# multiple_valve_controller_v2_0.net
KiCad netlist of a schematic drawn in EAGLE
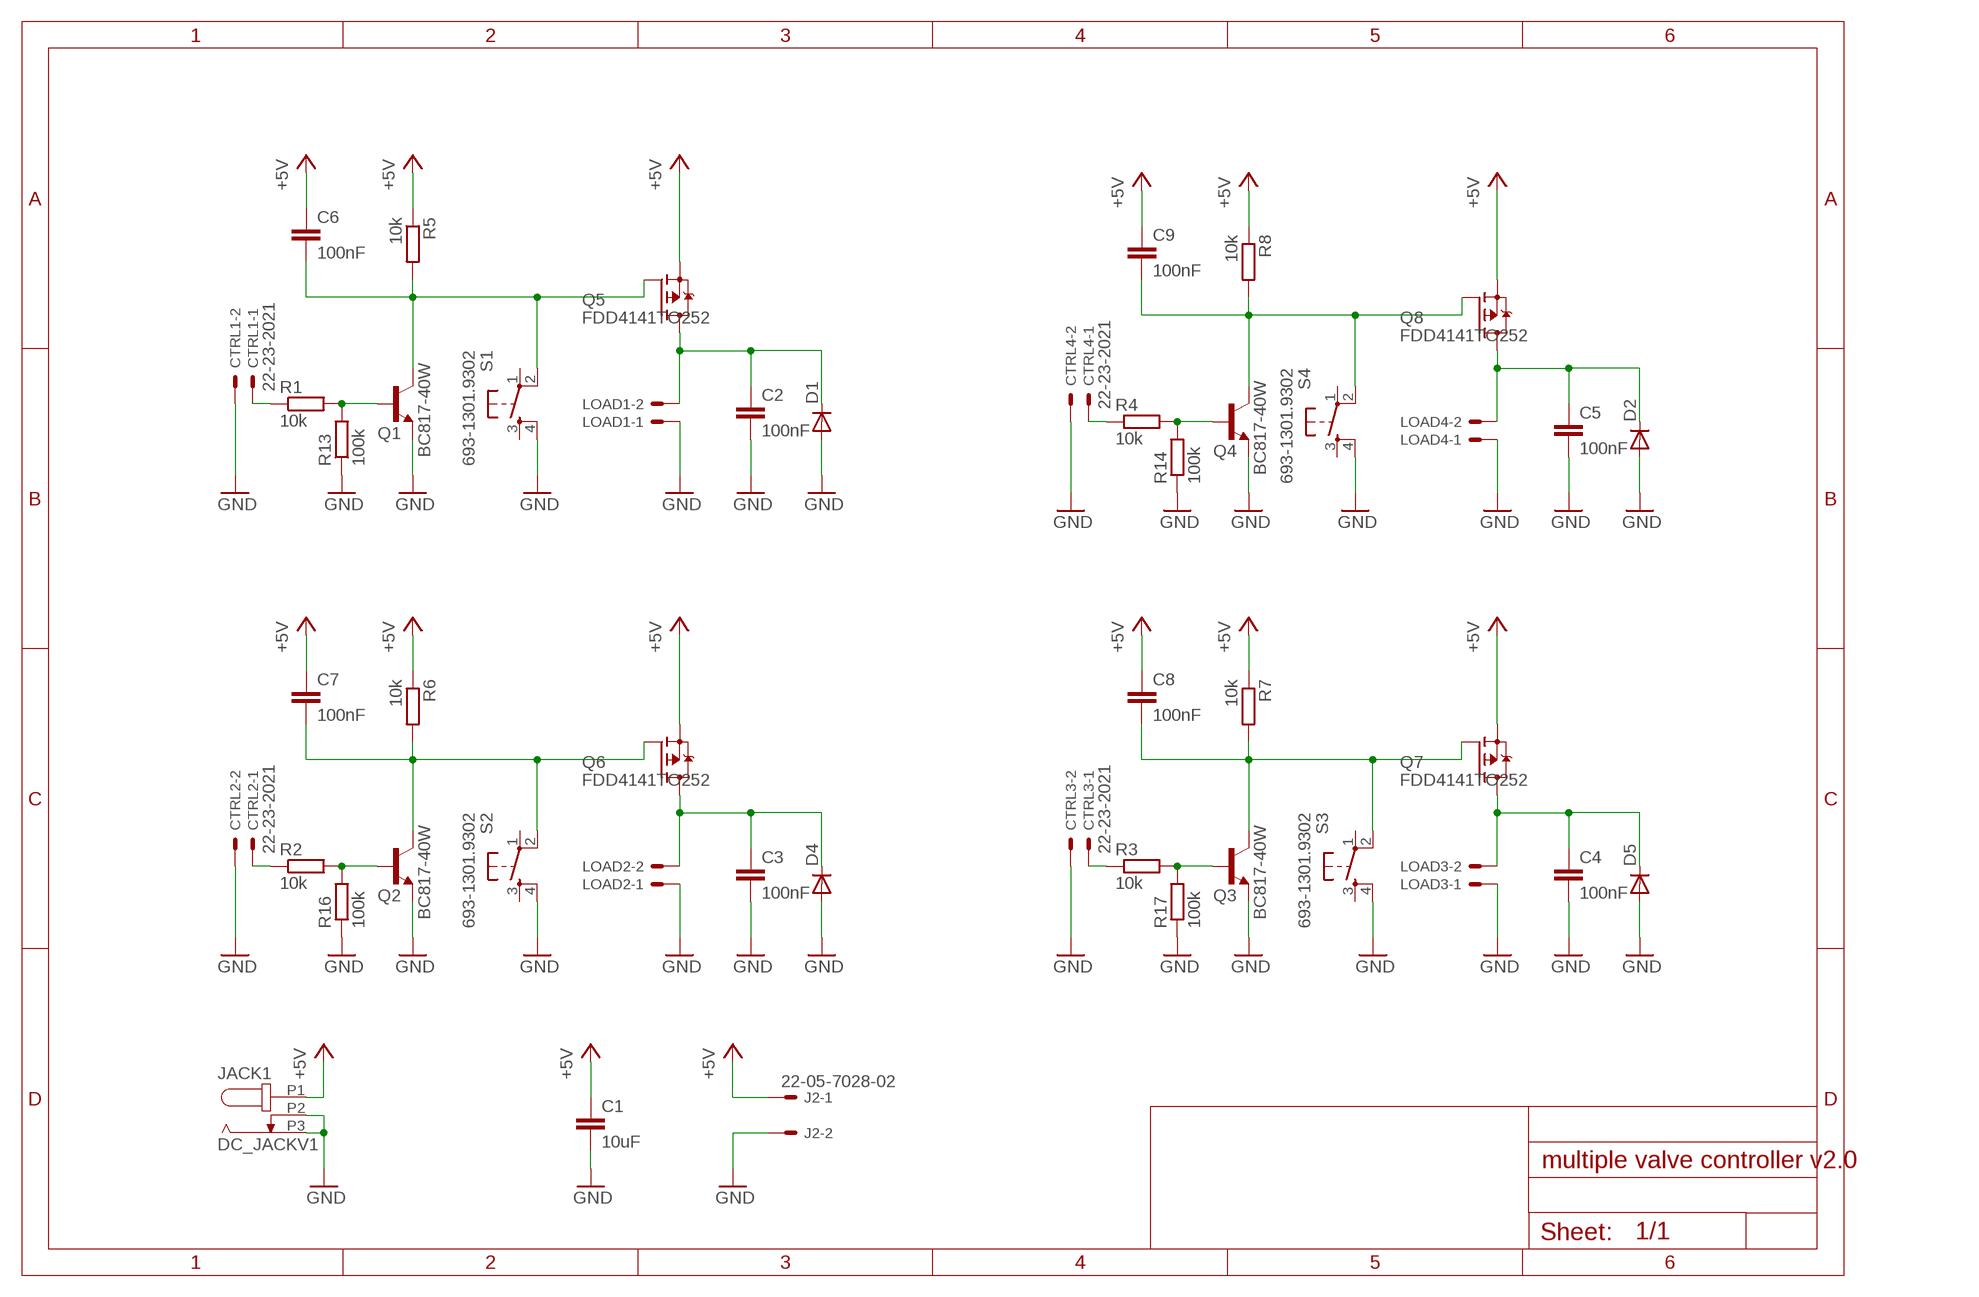
[diagram p0: schematic, sheet 1, part 1 of 2]
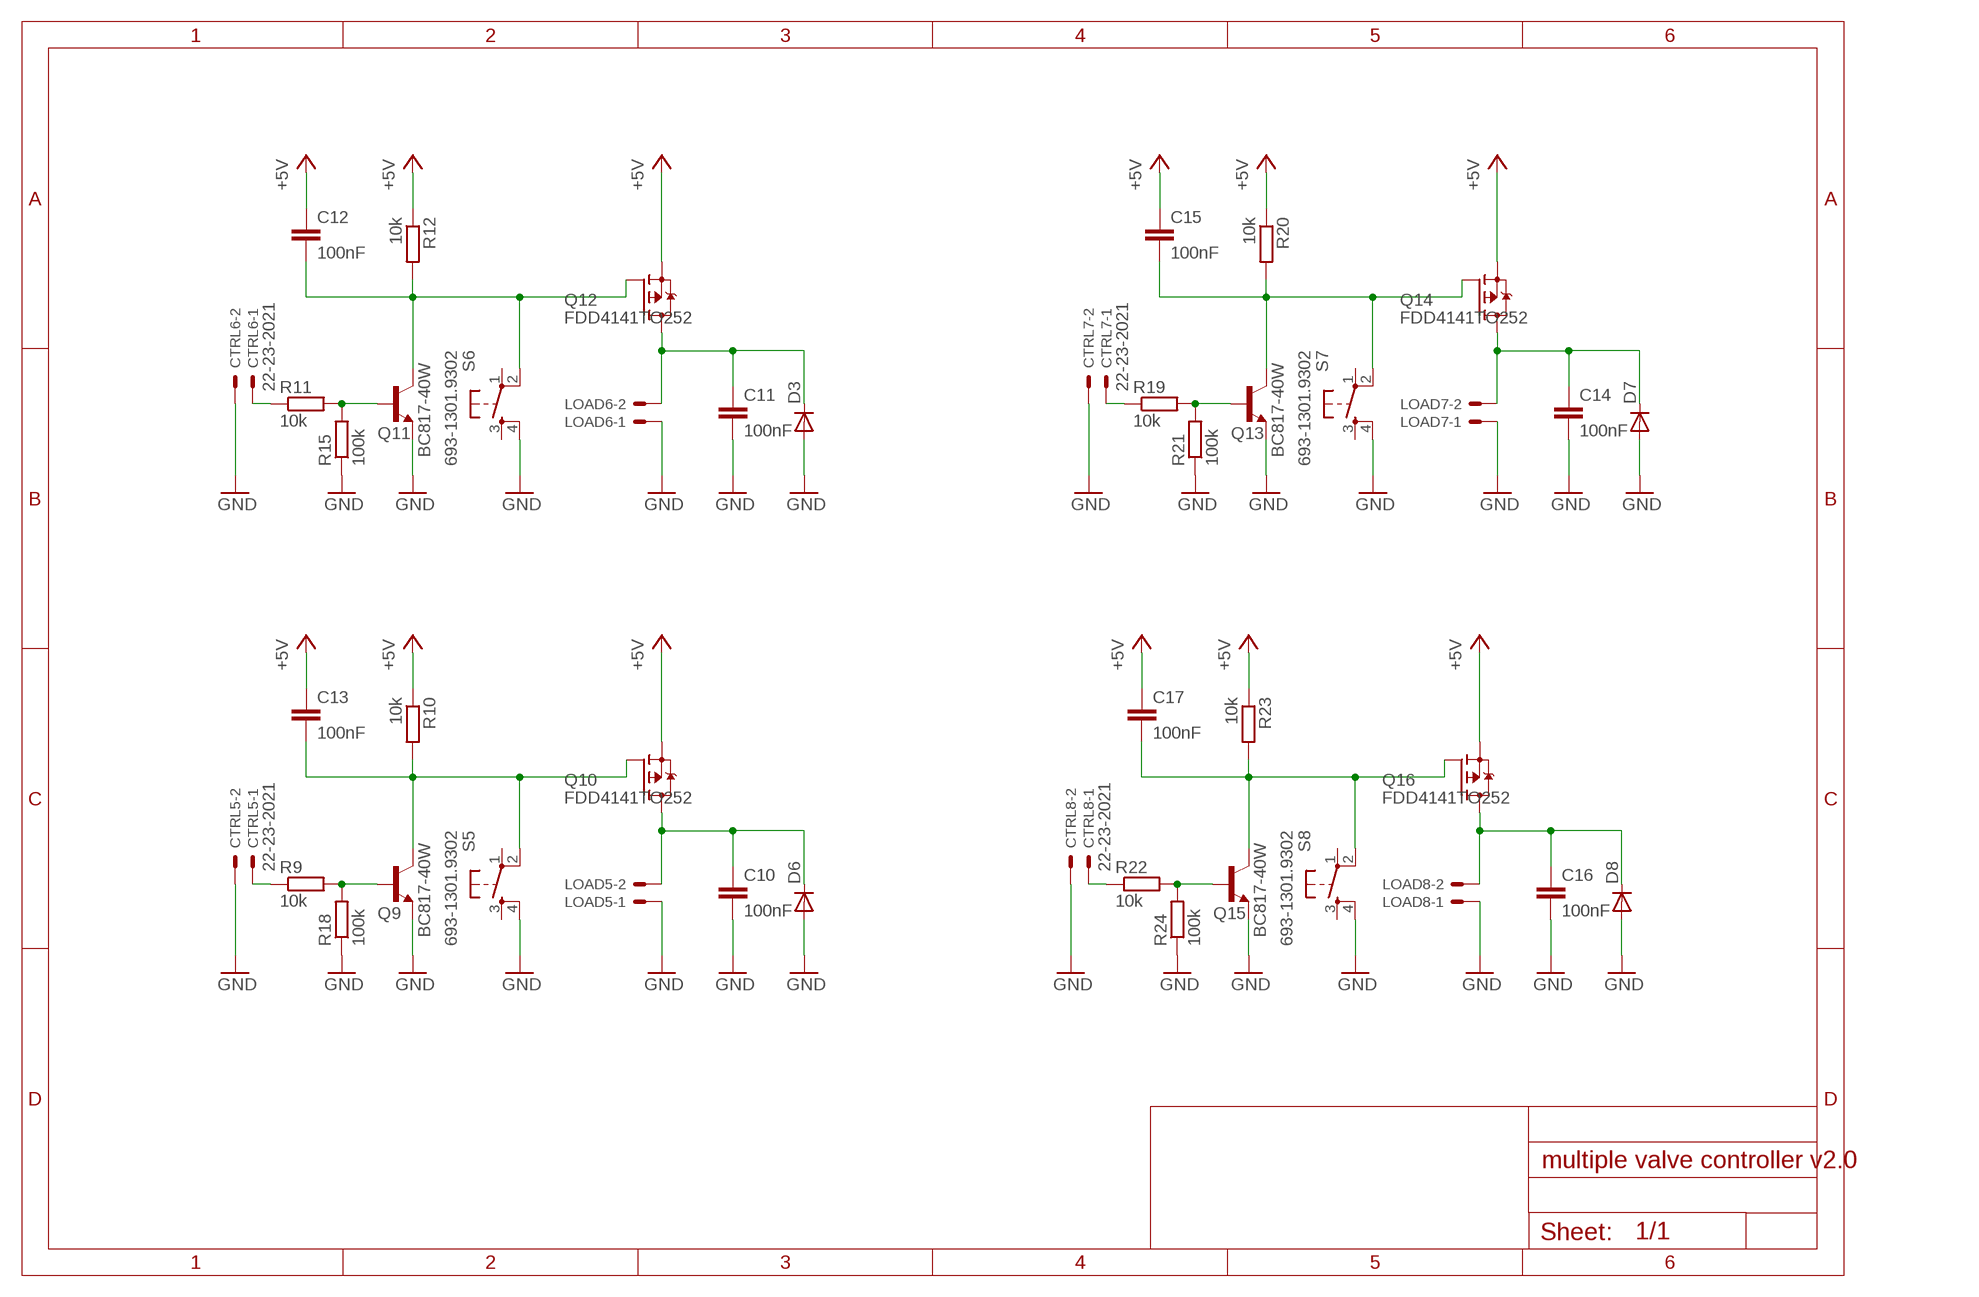
[diagram p1: schematic, sheet 1, part 2 of 2]

(export (version "E")
  (design (tool "Eeschema 10.0.6"))
  (components
    (comp (ref "C1")
      (value "10uF")
      (footprint "eagle-import:C1210")
      (libsource (lib "eagle-import") (part "C-EUC1210"))
    )
    (comp (ref "C2")
      (value "100nF")
      (footprint "eagle-import:C1210")
      (libsource (lib "eagle-import") (part "C-EUC1210"))
    )
    (comp (ref "C3")
      (value "100nF")
      (footprint "eagle-import:C1210")
      (libsource (lib "eagle-import") (part "C-EUC1210"))
    )
    (comp (ref "C4")
      (value "100nF")
      (footprint "eagle-import:C1210")
      (libsource (lib "eagle-import") (part "C-EUC1210"))
    )
    (comp (ref "C5")
      (value "100nF")
      (footprint "eagle-import:C1210")
      (libsource (lib "eagle-import") (part "C-EUC1210"))
    )
    (comp (ref "C6")
      (value "100nF")
      (footprint "eagle-import:C0603")
      (libsource (lib "eagle-import") (part "C-EUC0603"))
    )
    (comp (ref "C7")
      (value "100nF")
      (footprint "eagle-import:C0603")
      (libsource (lib "eagle-import") (part "C-EUC0603"))
    )
    (comp (ref "C8")
      (value "100nF")
      (footprint "eagle-import:C0603")
      (libsource (lib "eagle-import") (part "C-EUC0603"))
    )
    (comp (ref "C9")
      (value "100nF")
      (footprint "eagle-import:C0603")
      (libsource (lib "eagle-import") (part "C-EUC0603"))
    )
    (comp (ref "C10")
      (value "100nF")
      (footprint "eagle-import:C1210")
      (libsource (lib "eagle-import") (part "C-EUC1210"))
    )
    (comp (ref "C11")
      (value "100nF")
      (footprint "eagle-import:C1210")
      (libsource (lib "eagle-import") (part "C-EUC1210"))
    )
    (comp (ref "C12")
      (value "100nF")
      (footprint "eagle-import:C0603")
      (libsource (lib "eagle-import") (part "C-EUC0603"))
    )
    (comp (ref "C13")
      (value "100nF")
      (footprint "eagle-import:C0603")
      (libsource (lib "eagle-import") (part "C-EUC0603"))
    )
    (comp (ref "C14")
      (value "100nF")
      (footprint "eagle-import:C1210")
      (libsource (lib "eagle-import") (part "C-EUC1210"))
    )
    (comp (ref "C15")
      (value "100nF")
      (footprint "eagle-import:C0603")
      (libsource (lib "eagle-import") (part "C-EUC0603"))
    )
    (comp (ref "C16")
      (value "100nF")
      (footprint "eagle-import:C1210")
      (libsource (lib "eagle-import") (part "C-EUC1210"))
    )
    (comp (ref "C17")
      (value "100nF")
      (footprint "eagle-import:C0603")
      (libsource (lib "eagle-import") (part "C-EUC0603"))
    )
    (comp (ref "CTRL1")
      (value "22-23-2021")
      (footprint "eagle-import:22-23-2021")
      (fields (field (name "MF") "MOLEX"))
      (libsource (lib "eagle-import") (part "con-molex_165_22-23-2021"))
    )
    (comp (ref "CTRL2")
      (value "22-23-2021")
      (footprint "eagle-import:22-23-2021")
      (fields (field (name "MF") "MOLEX"))
      (libsource (lib "eagle-import") (part "con-molex_165_22-23-2021"))
    )
    (comp (ref "CTRL3")
      (value "22-23-2021")
      (footprint "eagle-import:22-23-2021")
      (fields (field (name "MF") "MOLEX"))
      (libsource (lib "eagle-import") (part "con-molex_165_22-23-2021"))
    )
    (comp (ref "CTRL4")
      (value "22-23-2021")
      (footprint "eagle-import:22-23-2021")
      (fields (field (name "MF") "MOLEX"))
      (libsource (lib "eagle-import") (part "con-molex_165_22-23-2021"))
    )
    (comp (ref "CTRL5")
      (value "22-23-2021")
      (footprint "eagle-import:22-23-2021")
      (fields (field (name "MF") "MOLEX"))
      (libsource (lib "eagle-import") (part "con-molex_165_22-23-2021"))
    )
    (comp (ref "CTRL6")
      (value "22-23-2021")
      (footprint "eagle-import:22-23-2021")
      (fields (field (name "MF") "MOLEX"))
      (libsource (lib "eagle-import") (part "con-molex_165_22-23-2021"))
    )
    (comp (ref "CTRL7")
      (value "22-23-2021")
      (footprint "eagle-import:22-23-2021")
      (fields (field (name "MF") "MOLEX"))
      (libsource (lib "eagle-import") (part "con-molex_165_22-23-2021"))
    )
    (comp (ref "CTRL8")
      (value "22-23-2021")
      (footprint "eagle-import:22-23-2021")
      (fields (field (name "MF") "MOLEX"))
      (libsource (lib "eagle-import") (part "con-molex_165_22-23-2021"))
    )
    (comp (ref "D1")
      (value "DIODE-SOD323-R")
      (footprint "eagle-import:SOD323-R")
      (libsource (lib "eagle-import") (part "DIODE-SOD323-R"))
    )
    (comp (ref "D2")
      (value "DIODE-SOD323-R")
      (footprint "eagle-import:SOD323-R")
      (libsource (lib "eagle-import") (part "DIODE-SOD323-R"))
    )
    (comp (ref "D3")
      (value "DIODE-SOD323-R")
      (footprint "eagle-import:SOD323-R")
      (libsource (lib "eagle-import") (part "DIODE-SOD323-R"))
    )
    (comp (ref "D4")
      (value "DIODE-SOD323-R")
      (footprint "eagle-import:SOD323-R")
      (libsource (lib "eagle-import") (part "DIODE-SOD323-R"))
    )
    (comp (ref "D5")
      (value "DIODE-SOD323-R")
      (footprint "eagle-import:SOD323-R")
      (libsource (lib "eagle-import") (part "DIODE-SOD323-R"))
    )
    (comp (ref "D6")
      (value "DIODE-SOD323-R")
      (footprint "eagle-import:SOD323-R")
      (libsource (lib "eagle-import") (part "DIODE-SOD323-R"))
    )
    (comp (ref "D7")
      (value "DIODE-SOD323-R")
      (footprint "eagle-import:SOD323-R")
      (libsource (lib "eagle-import") (part "DIODE-SOD323-R"))
    )
    (comp (ref "D8")
      (value "DIODE-SOD323-R")
      (footprint "eagle-import:SOD323-R")
      (libsource (lib "eagle-import") (part "DIODE-SOD323-R"))
    )
    (comp (ref "J2")
      (value "22-05-7028-02")
      (footprint "eagle-import:7395-02")
      (libsource (lib "eagle-import") (part "22-?-0205-7028"))
    )
    (comp (ref "JACK1")
      (value "DC_JACKV1")
      (footprint "eagle-import:DC_POWER_INPUT")
      (libsource (lib "eagle-import") (part "DC_JACKV1"))
    )
    (comp (ref "LOAD1")
      (value "22-23-2021")
      (footprint "eagle-import:22-23-2021")
      (fields (field (name "MF") "MOLEX"))
      (libsource (lib "eagle-import") (part "22-23-2021"))
    )
    (comp (ref "LOAD2")
      (value "22-23-2021")
      (footprint "eagle-import:22-23-2021")
      (fields (field (name "MF") "MOLEX"))
      (libsource (lib "eagle-import") (part "22-23-2021"))
    )
    (comp (ref "LOAD3")
      (value "22-23-2021")
      (footprint "eagle-import:22-23-2021")
      (fields (field (name "MF") "MOLEX"))
      (libsource (lib "eagle-import") (part "22-23-2021"))
    )
    (comp (ref "LOAD4")
      (value "22-23-2021")
      (footprint "eagle-import:22-23-2021")
      (fields (field (name "MF") "MOLEX"))
      (libsource (lib "eagle-import") (part "22-23-2021"))
    )
    (comp (ref "LOAD5")
      (value "22-23-2021")
      (footprint "eagle-import:22-23-2021")
      (fields (field (name "MF") "MOLEX"))
      (libsource (lib "eagle-import") (part "22-23-2021"))
    )
    (comp (ref "LOAD6")
      (value "22-23-2021")
      (footprint "eagle-import:22-23-2021")
      (fields (field (name "MF") "MOLEX"))
      (libsource (lib "eagle-import") (part "22-23-2021"))
    )
    (comp (ref "LOAD7")
      (value "22-23-2021")
      (footprint "eagle-import:22-23-2021")
      (fields (field (name "MF") "MOLEX"))
      (libsource (lib "eagle-import") (part "22-23-2021"))
    )
    (comp (ref "LOAD8")
      (value "22-23-2021")
      (footprint "eagle-import:22-23-2021")
      (fields (field (name "MF") "MOLEX"))
      (libsource (lib "eagle-import") (part "22-23-2021"))
    )
    (comp (ref "Q1")
      (value "BC817-40W")
      (footprint "eagle-import:SOT323-BEC")
      (libsource (lib "eagle-import") (part "BC817"))
    )
    (comp (ref "Q2")
      (value "BC817-40W")
      (footprint "eagle-import:SOT323-BEC")
      (libsource (lib "eagle-import") (part "BC817"))
    )
    (comp (ref "Q3")
      (value "BC817-40W")
      (footprint "eagle-import:SOT323-BEC")
      (libsource (lib "eagle-import") (part "BC817"))
    )
    (comp (ref "Q4")
      (value "BC817-40W")
      (footprint "eagle-import:SOT323-BEC")
      (libsource (lib "eagle-import") (part "BC817"))
    )
    (comp (ref "Q5")
      (value "FDD4141TO252")
      (footprint "eagle-import:TO252")
      (libsource (lib "eagle-import") (part "FDD4141TO252"))
    )
    (comp (ref "Q6")
      (value "FDD4141TO252")
      (footprint "eagle-import:TO252")
      (libsource (lib "eagle-import") (part "FDD4141TO252"))
    )
    (comp (ref "Q7")
      (value "FDD4141TO252")
      (footprint "eagle-import:TO252")
      (libsource (lib "eagle-import") (part "FDD4141TO252"))
    )
    (comp (ref "Q8")
      (value "FDD4141TO252")
      (footprint "eagle-import:TO252")
      (libsource (lib "eagle-import") (part "FDD4141TO252"))
    )
    (comp (ref "Q9")
      (value "BC817-40W")
      (footprint "eagle-import:SOT323-BEC")
      (libsource (lib "eagle-import") (part "BC817"))
    )
    (comp (ref "Q10")
      (value "FDD4141TO252")
      (footprint "eagle-import:TO252")
      (libsource (lib "eagle-import") (part "FDD4141TO252"))
    )
    (comp (ref "Q11")
      (value "BC817-40W")
      (footprint "eagle-import:SOT323-BEC")
      (libsource (lib "eagle-import") (part "BC817"))
    )
    (comp (ref "Q12")
      (value "FDD4141TO252")
      (footprint "eagle-import:TO252")
      (libsource (lib "eagle-import") (part "FDD4141TO252"))
    )
    (comp (ref "Q13")
      (value "BC817-40W")
      (footprint "eagle-import:SOT323-BEC")
      (libsource (lib "eagle-import") (part "BC817"))
    )
    (comp (ref "Q14")
      (value "FDD4141TO252")
      (footprint "eagle-import:TO252")
      (libsource (lib "eagle-import") (part "FDD4141TO252"))
    )
    (comp (ref "Q15")
      (value "BC817-40W")
      (footprint "eagle-import:SOT323-BEC")
      (libsource (lib "eagle-import") (part "BC817"))
    )
    (comp (ref "Q16")
      (value "FDD4141TO252")
      (footprint "eagle-import:TO252")
      (libsource (lib "eagle-import") (part "FDD4141TO252"))
    )
    (comp (ref "R1")
      (value "10k")
      (footprint "eagle-import:R0402")
      (libsource (lib "eagle-import") (part "R-EU_R0402"))
    )
    (comp (ref "R2")
      (value "10k")
      (footprint "eagle-import:R0402")
      (libsource (lib "eagle-import") (part "R-EU_R0402"))
    )
    (comp (ref "R3")
      (value "10k")
      (footprint "eagle-import:R0402")
      (libsource (lib "eagle-import") (part "R-EU_R0402"))
    )
    (comp (ref "R4")
      (value "10k")
      (footprint "eagle-import:R0402")
      (libsource (lib "eagle-import") (part "R-EU_R0402"))
    )
    (comp (ref "R5")
      (value "10k")
      (footprint "eagle-import:R0603")
      (libsource (lib "eagle-import") (part "R-EU_R0603"))
    )
    (comp (ref "R6")
      (value "10k")
      (footprint "eagle-import:R0603")
      (libsource (lib "eagle-import") (part "R-EU_R0603"))
    )
    (comp (ref "R7")
      (value "10k")
      (footprint "eagle-import:R0603")
      (libsource (lib "eagle-import") (part "R-EU_R0603"))
    )
    (comp (ref "R8")
      (value "10k")
      (footprint "eagle-import:R0603")
      (libsource (lib "eagle-import") (part "R-EU_R0603"))
    )
    (comp (ref "R9")
      (value "10k")
      (footprint "eagle-import:R0402")
      (libsource (lib "eagle-import") (part "R-EU_R0402"))
    )
    (comp (ref "R10")
      (value "10k")
      (footprint "eagle-import:R0603")
      (libsource (lib "eagle-import") (part "R-EU_R0603"))
    )
    (comp (ref "R11")
      (value "10k")
      (footprint "eagle-import:R0402")
      (libsource (lib "eagle-import") (part "R-EU_R0402"))
    )
    (comp (ref "R12")
      (value "10k")
      (footprint "eagle-import:R0603")
      (libsource (lib "eagle-import") (part "R-EU_R0603"))
    )
    (comp (ref "R13")
      (value "100k")
      (footprint "eagle-import:R0402")
      (libsource (lib "eagle-import") (part "R-EU_R0402"))
    )
    (comp (ref "R14")
      (value "100k")
      (footprint "eagle-import:R0402")
      (libsource (lib "eagle-import") (part "R-EU_R0402"))
    )
    (comp (ref "R15")
      (value "100k")
      (footprint "eagle-import:R0402")
      (libsource (lib "eagle-import") (part "R-EU_R0402"))
    )
    (comp (ref "R16")
      (value "100k")
      (footprint "eagle-import:R0402")
      (libsource (lib "eagle-import") (part "R-EU_R0402"))
    )
    (comp (ref "R17")
      (value "100k")
      (footprint "eagle-import:R0402")
      (libsource (lib "eagle-import") (part "R-EU_R0402"))
    )
    (comp (ref "R18")
      (value "100k")
      (footprint "eagle-import:R0402")
      (libsource (lib "eagle-import") (part "R-EU_R0402"))
    )
    (comp (ref "R19")
      (value "10k")
      (footprint "eagle-import:R0402")
      (libsource (lib "eagle-import") (part "R-EU_R0402"))
    )
    (comp (ref "R20")
      (value "10k")
      (footprint "eagle-import:R0603")
      (libsource (lib "eagle-import") (part "R-EU_R0603"))
    )
    (comp (ref "R21")
      (value "100k")
      (footprint "eagle-import:R0402")
      (libsource (lib "eagle-import") (part "R-EU_R0402"))
    )
    (comp (ref "R22")
      (value "10k")
      (footprint "eagle-import:R0402")
      (libsource (lib "eagle-import") (part "R-EU_R0402"))
    )
    (comp (ref "R23")
      (value "10k")
      (footprint "eagle-import:R0603")
      (libsource (lib "eagle-import") (part "R-EU_R0603"))
    )
    (comp (ref "R24")
      (value "100k")
      (footprint "eagle-import:R0402")
      (libsource (lib "eagle-import") (part "R-EU_R0402"))
    )
    (comp (ref "S1")
      (value "693-1301.9302")
      (footprint "eagle-import:TACTILE-PTH")
      (libsource (lib "eagle-import") (part "TAC_SWITCHPTH"))
    )
    (comp (ref "S2")
      (value "693-1301.9302")
      (footprint "eagle-import:TACTILE-PTH")
      (libsource (lib "eagle-import") (part "TAC_SWITCHPTH"))
    )
    (comp (ref "S3")
      (value "693-1301.9302")
      (footprint "eagle-import:TACTILE-PTH")
      (libsource (lib "eagle-import") (part "TAC_SWITCHPTH"))
    )
    (comp (ref "S4")
      (value "693-1301.9302")
      (footprint "eagle-import:TACTILE-PTH")
      (libsource (lib "eagle-import") (part "TAC_SWITCHPTH"))
    )
    (comp (ref "S5")
      (value "693-1301.9302")
      (footprint "eagle-import:TACTILE-PTH")
      (libsource (lib "eagle-import") (part "TAC_SWITCHPTH"))
    )
    (comp (ref "S6")
      (value "693-1301.9302")
      (footprint "eagle-import:TACTILE-PTH")
      (libsource (lib "eagle-import") (part "TAC_SWITCHPTH"))
    )
    (comp (ref "S7")
      (value "693-1301.9302")
      (footprint "eagle-import:TACTILE-PTH")
      (libsource (lib "eagle-import") (part "TAC_SWITCHPTH"))
    )
    (comp (ref "S8")
      (value "693-1301.9302")
      (footprint "eagle-import:TACTILE-PTH")
      (libsource (lib "eagle-import") (part "TAC_SWITCHPTH"))
    )
  )
  (nets
    (net (code "1") (name "+5V") (class "Default")
      (node (ref "C1") (pin "1") (pinfunction "1_1") (pintype "passive"))
      (node (ref "C12") (pin "1") (pinfunction "1_1") (pintype "passive"))
      (node (ref "C13") (pin "1") (pinfunction "1_1") (pintype "passive"))
      (node (ref "C15") (pin "1") (pinfunction "1_1") (pintype "passive"))
      (node (ref "C17") (pin "1") (pinfunction "1_1") (pintype "passive"))
      (node (ref "C6") (pin "1") (pinfunction "1_1") (pintype "passive"))
      (node (ref "C7") (pin "1") (pinfunction "1_1") (pintype "passive"))
      (node (ref "C8") (pin "1") (pinfunction "1_1") (pintype "passive"))
      (node (ref "C9") (pin "1") (pinfunction "1_1") (pintype "passive"))
      (node (ref "J2") (pin "1") (pinfunction "S_1") (pintype "passive"))
      (node (ref "JACK1") (pin "P1") (pinfunction "1_P1") (pintype "passive"))
      (node (ref "Q10") (pin "2") (pinfunction "S_2") (pintype "passive"))
      (node (ref "Q12") (pin "2") (pinfunction "S_2") (pintype "passive"))
      (node (ref "Q14") (pin "2") (pinfunction "S_2") (pintype "passive"))
      (node (ref "Q16") (pin "2") (pinfunction "S_2") (pintype "passive"))
      (node (ref "Q5") (pin "2") (pinfunction "S_2") (pintype "passive"))
      (node (ref "Q6") (pin "2") (pinfunction "S_2") (pintype "passive"))
      (node (ref "Q7") (pin "2") (pinfunction "S_2") (pintype "passive"))
      (node (ref "Q8") (pin "2") (pinfunction "S_2") (pintype "passive"))
      (node (ref "R10") (pin "1") (pinfunction "1_1") (pintype "passive"))
      (node (ref "R12") (pin "1") (pinfunction "1_1") (pintype "passive"))
      (node (ref "R20") (pin "1") (pinfunction "1_1") (pintype "passive"))
      (node (ref "R23") (pin "1") (pinfunction "1_1") (pintype "passive"))
      (node (ref "R5") (pin "1") (pinfunction "1_1") (pintype "passive"))
      (node (ref "R6") (pin "1") (pinfunction "1_1") (pintype "passive"))
      (node (ref "R7") (pin "1") (pinfunction "1_1") (pintype "passive"))
      (node (ref "R8") (pin "1") (pinfunction "1_1") (pintype "passive"))
    )
    (net (code "2") (name "GND") (class "Default")
      (node (ref "C1") (pin "2") (pinfunction "2_2") (pintype "passive"))
      (node (ref "C10") (pin "2") (pinfunction "2_2") (pintype "passive"))
      (node (ref "C11") (pin "2") (pinfunction "2_2") (pintype "passive"))
      (node (ref "C14") (pin "2") (pinfunction "2_2") (pintype "passive"))
      (node (ref "C16") (pin "2") (pinfunction "2_2") (pintype "passive"))
      (node (ref "C2") (pin "2") (pinfunction "2_2") (pintype "passive"))
      (node (ref "C3") (pin "2") (pinfunction "2_2") (pintype "passive"))
      (node (ref "C4") (pin "2") (pinfunction "2_2") (pintype "passive"))
      (node (ref "C5") (pin "2") (pinfunction "2_2") (pintype "passive"))
      (node (ref "CTRL1") (pin "2") (pinfunction "S_2") (pintype "passive"))
      (node (ref "CTRL2") (pin "2") (pinfunction "S_2") (pintype "passive"))
      (node (ref "CTRL3") (pin "2") (pinfunction "S_2") (pintype "passive"))
      (node (ref "CTRL4") (pin "2") (pinfunction "S_2") (pintype "passive"))
      (node (ref "CTRL5") (pin "2") (pinfunction "S_2") (pintype "passive"))
      (node (ref "CTRL6") (pin "2") (pinfunction "S_2") (pintype "passive"))
      (node (ref "CTRL7") (pin "2") (pinfunction "S_2") (pintype "passive"))
      (node (ref "CTRL8") (pin "2") (pinfunction "S_2") (pintype "passive"))
      (node (ref "D1") (pin "A") (pinfunction "A_A") (pintype "passive"))
      (node (ref "D2") (pin "A") (pinfunction "A_A") (pintype "passive"))
      (node (ref "D3") (pin "A") (pinfunction "A_A") (pintype "passive"))
      (node (ref "D4") (pin "A") (pinfunction "A_A") (pintype "passive"))
      (node (ref "D5") (pin "A") (pinfunction "A_A") (pintype "passive"))
      (node (ref "D6") (pin "A") (pinfunction "A_A") (pintype "passive"))
      (node (ref "D7") (pin "A") (pinfunction "A_A") (pintype "passive"))
      (node (ref "D8") (pin "A") (pinfunction "A_A") (pintype "passive"))
      (node (ref "J2") (pin "2") (pinfunction "S_2") (pintype "passive"))
      (node (ref "JACK1") (pin "P2") (pinfunction "2_P2") (pintype "passive"))
      (node (ref "JACK1") (pin "P3") (pinfunction "3_P3") (pintype "passive"))
      (node (ref "LOAD1") (pin "1") (pinfunction "S_1") (pintype "passive"))
      (node (ref "LOAD2") (pin "1") (pinfunction "S_1") (pintype "passive"))
      (node (ref "LOAD3") (pin "1") (pinfunction "S_1") (pintype "passive"))
      (node (ref "LOAD4") (pin "1") (pinfunction "S_1") (pintype "passive"))
      (node (ref "LOAD5") (pin "1") (pinfunction "S_1") (pintype "passive"))
      (node (ref "LOAD6") (pin "1") (pinfunction "S_1") (pintype "passive"))
      (node (ref "LOAD7") (pin "1") (pinfunction "S_1") (pintype "passive"))
      (node (ref "LOAD8") (pin "1") (pinfunction "S_1") (pintype "passive"))
      (node (ref "Q1") (pin "E") (pinfunction "E_E") (pintype "passive"))
      (node (ref "Q11") (pin "E") (pinfunction "E_E") (pintype "passive"))
      (node (ref "Q13") (pin "E") (pinfunction "E_E") (pintype "passive"))
      (node (ref "Q15") (pin "E") (pinfunction "E_E") (pintype "passive"))
      (node (ref "Q2") (pin "E") (pinfunction "E_E") (pintype "passive"))
      (node (ref "Q3") (pin "E") (pinfunction "E_E") (pintype "passive"))
      (node (ref "Q4") (pin "E") (pinfunction "E_E") (pintype "passive"))
      (node (ref "Q9") (pin "E") (pinfunction "E_E") (pintype "passive"))
      (node (ref "R13") (pin "1") (pinfunction "1_1") (pintype "passive"))
      (node (ref "R14") (pin "1") (pinfunction "1_1") (pintype "passive"))
      (node (ref "R15") (pin "1") (pinfunction "1_1") (pintype "passive"))
      (node (ref "R16") (pin "1") (pinfunction "1_1") (pintype "passive"))
      (node (ref "R17") (pin "1") (pinfunction "1_1") (pintype "passive"))
      (node (ref "R18") (pin "1") (pinfunction "1_1") (pintype "passive"))
      (node (ref "R21") (pin "1") (pinfunction "1_1") (pintype "passive"))
      (node (ref "R24") (pin "1") (pinfunction "1_1") (pintype "passive"))
      (node (ref "S1") (pin "4") (pinfunction "4_4") (pintype "passive"))
      (node (ref "S2") (pin "4") (pinfunction "4_4") (pintype "passive"))
      (node (ref "S3") (pin "4") (pinfunction "4_4") (pintype "passive"))
      (node (ref "S4") (pin "4") (pinfunction "4_4") (pintype "passive"))
      (node (ref "S5") (pin "4") (pinfunction "4_4") (pintype "passive"))
      (node (ref "S6") (pin "4") (pinfunction "4_4") (pintype "passive"))
      (node (ref "S7") (pin "4") (pinfunction "4_4") (pintype "passive"))
      (node (ref "S8") (pin "4") (pinfunction "4_4") (pintype "passive"))
    )
    (net (code "3") (name "Net-(CTRL1A-S)") (class "Default")
      (node (ref "CTRL1") (pin "1") (pinfunction "S_1") (pintype "passive"))
      (node (ref "R1") (pin "1") (pinfunction "1_1") (pintype "passive"))
    )
    (net (code "4") (name "Net-(CTRL2A-S)") (class "Default")
      (node (ref "CTRL2") (pin "1") (pinfunction "S_1") (pintype "passive"))
      (node (ref "R2") (pin "1") (pinfunction "1_1") (pintype "passive"))
    )
    (net (code "5") (name "Net-(CTRL3A-S)") (class "Default")
      (node (ref "CTRL3") (pin "1") (pinfunction "S_1") (pintype "passive"))
      (node (ref "R3") (pin "1") (pinfunction "1_1") (pintype "passive"))
    )
    (net (code "6") (name "Net-(CTRL4A-S)") (class "Default")
      (node (ref "CTRL4") (pin "1") (pinfunction "S_1") (pintype "passive"))
      (node (ref "R4") (pin "1") (pinfunction "1_1") (pintype "passive"))
    )
    (net (code "7") (name "Net-(CTRL5A-S)") (class "Default")
      (node (ref "CTRL5") (pin "1") (pinfunction "S_1") (pintype "passive"))
      (node (ref "R9") (pin "1") (pinfunction "1_1") (pintype "passive"))
    )
    (net (code "8") (name "Net-(CTRL6A-S)") (class "Default")
      (node (ref "CTRL6") (pin "1") (pinfunction "S_1") (pintype "passive"))
      (node (ref "R11") (pin "1") (pinfunction "1_1") (pintype "passive"))
    )
    (net (code "9") (name "Net-(CTRL7A-S)") (class "Default")
      (node (ref "CTRL7") (pin "1") (pinfunction "S_1") (pintype "passive"))
      (node (ref "R19") (pin "1") (pinfunction "1_1") (pintype "passive"))
    )
    (net (code "10") (name "Net-(CTRL8A-S)") (class "Default")
      (node (ref "CTRL8") (pin "1") (pinfunction "S_1") (pintype "passive"))
      (node (ref "R22") (pin "1") (pinfunction "1_1") (pintype "passive"))
    )
    (net (code "11") (name "Net-(LOAD1B-S)") (class "Default")
      (node (ref "C2") (pin "1") (pinfunction "1_1") (pintype "passive"))
      (node (ref "D1") (pin "C") (pinfunction "C_C") (pintype "passive"))
      (node (ref "LOAD1") (pin "2") (pinfunction "S_2") (pintype "passive"))
      (node (ref "Q5") (pin "3") (pinfunction "D_3") (pintype "passive"))
    )
    (net (code "12") (name "Net-(LOAD2B-S)") (class "Default")
      (node (ref "C3") (pin "1") (pinfunction "1_1") (pintype "passive"))
      (node (ref "D4") (pin "C") (pinfunction "C_C") (pintype "passive"))
      (node (ref "LOAD2") (pin "2") (pinfunction "S_2") (pintype "passive"))
      (node (ref "Q6") (pin "3") (pinfunction "D_3") (pintype "passive"))
    )
    (net (code "13") (name "Net-(LOAD3B-S)") (class "Default")
      (node (ref "C4") (pin "1") (pinfunction "1_1") (pintype "passive"))
      (node (ref "D5") (pin "C") (pinfunction "C_C") (pintype "passive"))
      (node (ref "LOAD3") (pin "2") (pinfunction "S_2") (pintype "passive"))
      (node (ref "Q7") (pin "3") (pinfunction "D_3") (pintype "passive"))
    )
    (net (code "14") (name "Net-(LOAD4B-S)") (class "Default")
      (node (ref "C5") (pin "1") (pinfunction "1_1") (pintype "passive"))
      (node (ref "D2") (pin "C") (pinfunction "C_C") (pintype "passive"))
      (node (ref "LOAD4") (pin "2") (pinfunction "S_2") (pintype "passive"))
      (node (ref "Q8") (pin "3") (pinfunction "D_3") (pintype "passive"))
    )
    (net (code "15") (name "Net-(LOAD5B-S)") (class "Default")
      (node (ref "C10") (pin "1") (pinfunction "1_1") (pintype "passive"))
      (node (ref "D6") (pin "C") (pinfunction "C_C") (pintype "passive"))
      (node (ref "LOAD5") (pin "2") (pinfunction "S_2") (pintype "passive"))
      (node (ref "Q10") (pin "3") (pinfunction "D_3") (pintype "passive"))
    )
    (net (code "16") (name "Net-(LOAD6B-S)") (class "Default")
      (node (ref "C11") (pin "1") (pinfunction "1_1") (pintype "passive"))
      (node (ref "D3") (pin "C") (pinfunction "C_C") (pintype "passive"))
      (node (ref "LOAD6") (pin "2") (pinfunction "S_2") (pintype "passive"))
      (node (ref "Q12") (pin "3") (pinfunction "D_3") (pintype "passive"))
    )
    (net (code "17") (name "Net-(LOAD7B-S)") (class "Default")
      (node (ref "C14") (pin "1") (pinfunction "1_1") (pintype "passive"))
      (node (ref "D7") (pin "C") (pinfunction "C_C") (pintype "passive"))
      (node (ref "LOAD7") (pin "2") (pinfunction "S_2") (pintype "passive"))
      (node (ref "Q14") (pin "3") (pinfunction "D_3") (pintype "passive"))
    )
    (net (code "18") (name "Net-(LOAD8B-S)") (class "Default")
      (node (ref "C16") (pin "1") (pinfunction "1_1") (pintype "passive"))
      (node (ref "D8") (pin "C") (pinfunction "C_C") (pintype "passive"))
      (node (ref "LOAD8") (pin "2") (pinfunction "S_2") (pintype "passive"))
      (node (ref "Q16") (pin "3") (pinfunction "D_3") (pintype "passive"))
    )
    (net (code "19") (name "Net-(Q1-PadB)") (class "Default")
      (node (ref "Q1") (pin "B") (pinfunction "B_B") (pintype "passive"))
      (node (ref "R1") (pin "2") (pinfunction "2_2") (pintype "passive"))
      (node (ref "R13") (pin "2") (pinfunction "2_2") (pintype "passive"))
    )
    (net (code "20") (name "Net-(Q2-PadB)") (class "Default")
      (node (ref "Q2") (pin "B") (pinfunction "B_B") (pintype "passive"))
      (node (ref "R16") (pin "2") (pinfunction "2_2") (pintype "passive"))
      (node (ref "R2") (pin "2") (pinfunction "2_2") (pintype "passive"))
    )
    (net (code "21") (name "Net-(Q3-PadB)") (class "Default")
      (node (ref "Q3") (pin "B") (pinfunction "B_B") (pintype "passive"))
      (node (ref "R17") (pin "2") (pinfunction "2_2") (pintype "passive"))
      (node (ref "R3") (pin "2") (pinfunction "2_2") (pintype "passive"))
    )
    (net (code "22") (name "Net-(Q4-PadB)") (class "Default")
      (node (ref "Q4") (pin "B") (pinfunction "B_B") (pintype "passive"))
      (node (ref "R14") (pin "2") (pinfunction "2_2") (pintype "passive"))
      (node (ref "R4") (pin "2") (pinfunction "2_2") (pintype "passive"))
    )
    (net (code "23") (name "Net-(Q5-G)") (class "Default")
      (node (ref "C6") (pin "2") (pinfunction "2_2") (pintype "passive"))
      (node (ref "Q1") (pin "C") (pinfunction "C_C") (pintype "passive"))
      (node (ref "Q5") (pin "1") (pinfunction "G_1") (pintype "passive"))
      (node (ref "R5") (pin "2") (pinfunction "2_2") (pintype "passive"))
      (node (ref "S1") (pin "2") (pinfunction "2_2") (pintype "passive"))
    )
    (net (code "24") (name "Net-(Q6-G)") (class "Default")
      (node (ref "C7") (pin "2") (pinfunction "2_2") (pintype "passive"))
      (node (ref "Q2") (pin "C") (pinfunction "C_C") (pintype "passive"))
      (node (ref "Q6") (pin "1") (pinfunction "G_1") (pintype "passive"))
      (node (ref "R6") (pin "2") (pinfunction "2_2") (pintype "passive"))
      (node (ref "S2") (pin "2") (pinfunction "2_2") (pintype "passive"))
    )
    (net (code "25") (name "Net-(Q7-G)") (class "Default")
      (node (ref "C8") (pin "2") (pinfunction "2_2") (pintype "passive"))
      (node (ref "Q3") (pin "C") (pinfunction "C_C") (pintype "passive"))
      (node (ref "Q7") (pin "1") (pinfunction "G_1") (pintype "passive"))
      (node (ref "R7") (pin "2") (pinfunction "2_2") (pintype "passive"))
      (node (ref "S3") (pin "2") (pinfunction "2_2") (pintype "passive"))
    )
    (net (code "26") (name "Net-(Q8-G)") (class "Default")
      (node (ref "C9") (pin "2") (pinfunction "2_2") (pintype "passive"))
      (node (ref "Q4") (pin "C") (pinfunction "C_C") (pintype "passive"))
      (node (ref "Q8") (pin "1") (pinfunction "G_1") (pintype "passive"))
      (node (ref "R8") (pin "2") (pinfunction "2_2") (pintype "passive"))
      (node (ref "S4") (pin "2") (pinfunction "2_2") (pintype "passive"))
    )
    (net (code "27") (name "Net-(Q9-PadB)") (class "Default")
      (node (ref "Q9") (pin "B") (pinfunction "B_B") (pintype "passive"))
      (node (ref "R18") (pin "2") (pinfunction "2_2") (pintype "passive"))
      (node (ref "R9") (pin "2") (pinfunction "2_2") (pintype "passive"))
    )
    (net (code "28") (name "Net-(Q10-G)") (class "Default")
      (node (ref "C13") (pin "2") (pinfunction "2_2") (pintype "passive"))
      (node (ref "Q10") (pin "1") (pinfunction "G_1") (pintype "passive"))
      (node (ref "Q9") (pin "C") (pinfunction "C_C") (pintype "passive"))
      (node (ref "R10") (pin "2") (pinfunction "2_2") (pintype "passive"))
      (node (ref "S5") (pin "2") (pinfunction "2_2") (pintype "passive"))
    )
    (net (code "29") (name "Net-(Q11-PadB)") (class "Default")
      (node (ref "Q11") (pin "B") (pinfunction "B_B") (pintype "passive"))
      (node (ref "R11") (pin "2") (pinfunction "2_2") (pintype "passive"))
      (node (ref "R15") (pin "2") (pinfunction "2_2") (pintype "passive"))
    )
    (net (code "30") (name "Net-(Q12-G)") (class "Default")
      (node (ref "C12") (pin "2") (pinfunction "2_2") (pintype "passive"))
      (node (ref "Q11") (pin "C") (pinfunction "C_C") (pintype "passive"))
      (node (ref "Q12") (pin "1") (pinfunction "G_1") (pintype "passive"))
      (node (ref "R12") (pin "2") (pinfunction "2_2") (pintype "passive"))
      (node (ref "S6") (pin "2") (pinfunction "2_2") (pintype "passive"))
    )
    (net (code "31") (name "Net-(Q13-PadB)") (class "Default")
      (node (ref "Q13") (pin "B") (pinfunction "B_B") (pintype "passive"))
      (node (ref "R19") (pin "2") (pinfunction "2_2") (pintype "passive"))
      (node (ref "R21") (pin "2") (pinfunction "2_2") (pintype "passive"))
    )
    (net (code "32") (name "Net-(Q14-G)") (class "Default")
      (node (ref "C15") (pin "2") (pinfunction "2_2") (pintype "passive"))
      (node (ref "Q13") (pin "C") (pinfunction "C_C") (pintype "passive"))
      (node (ref "Q14") (pin "1") (pinfunction "G_1") (pintype "passive"))
      (node (ref "R20") (pin "2") (pinfunction "2_2") (pintype "passive"))
      (node (ref "S7") (pin "2") (pinfunction "2_2") (pintype "passive"))
    )
    (net (code "33") (name "Net-(Q15-PadB)") (class "Default")
      (node (ref "Q15") (pin "B") (pinfunction "B_B") (pintype "passive"))
      (node (ref "R22") (pin "2") (pinfunction "2_2") (pintype "passive"))
      (node (ref "R24") (pin "2") (pinfunction "2_2") (pintype "passive"))
    )
    (net (code "34") (name "Net-(Q16-G)") (class "Default")
      (node (ref "C17") (pin "2") (pinfunction "2_2") (pintype "passive"))
      (node (ref "Q15") (pin "C") (pinfunction "C_C") (pintype "passive"))
      (node (ref "Q16") (pin "1") (pinfunction "G_1") (pintype "passive"))
      (node (ref "R23") (pin "2") (pinfunction "2_2") (pintype "passive"))
      (node (ref "S8") (pin "2") (pinfunction "2_2") (pintype "passive"))
    )
    (net (code "35") (name "unconnected-(S1-Pad1)") (class "Default")
      (node (ref "S1") (pin "1") (pinfunction "1_1") (pintype "passive"))
    )
    (net (code "36") (name "unconnected-(S1-Pad3)") (class "Default")
      (node (ref "S1") (pin "3") (pinfunction "3_3") (pintype "passive"))
    )
    (net (code "37") (name "unconnected-(S2-Pad1)") (class "Default")
      (node (ref "S2") (pin "1") (pinfunction "1_1") (pintype "passive"))
    )
    (net (code "38") (name "unconnected-(S2-Pad3)") (class "Default")
      (node (ref "S2") (pin "3") (pinfunction "3_3") (pintype "passive"))
    )
    (net (code "39") (name "unconnected-(S3-Pad1)") (class "Default")
      (node (ref "S3") (pin "1") (pinfunction "1_1") (pintype "passive"))
    )
    (net (code "40") (name "unconnected-(S3-Pad3)") (class "Default")
      (node (ref "S3") (pin "3") (pinfunction "3_3") (pintype "passive"))
    )
    (net (code "41") (name "unconnected-(S4-Pad1)") (class "Default")
      (node (ref "S4") (pin "1") (pinfunction "1_1") (pintype "passive"))
    )
    (net (code "42") (name "unconnected-(S4-Pad3)") (class "Default")
      (node (ref "S4") (pin "3") (pinfunction "3_3") (pintype "passive"))
    )
    (net (code "43") (name "unconnected-(S5-Pad1)") (class "Default")
      (node (ref "S5") (pin "1") (pinfunction "1_1") (pintype "passive"))
    )
    (net (code "44") (name "unconnected-(S5-Pad3)") (class "Default")
      (node (ref "S5") (pin "3") (pinfunction "3_3") (pintype "passive"))
    )
    (net (code "45") (name "unconnected-(S6-Pad1)") (class "Default")
      (node (ref "S6") (pin "1") (pinfunction "1_1") (pintype "passive"))
    )
    (net (code "46") (name "unconnected-(S6-Pad3)") (class "Default")
      (node (ref "S6") (pin "3") (pinfunction "3_3") (pintype "passive"))
    )
    (net (code "47") (name "unconnected-(S7-Pad1)") (class "Default")
      (node (ref "S7") (pin "1") (pinfunction "1_1") (pintype "passive"))
    )
    (net (code "48") (name "unconnected-(S7-Pad3)") (class "Default")
      (node (ref "S7") (pin "3") (pinfunction "3_3") (pintype "passive"))
    )
    (net (code "49") (name "unconnected-(S8-Pad1)") (class "Default")
      (node (ref "S8") (pin "1") (pinfunction "1_1") (pintype "passive"))
    )
    (net (code "50") (name "unconnected-(S8-Pad3)") (class "Default")
      (node (ref "S8") (pin "3") (pinfunction "3_3") (pintype "passive"))
    )
  )
)
